# Power.net
KiCad netlist of a schematic drawn in Altium Designer
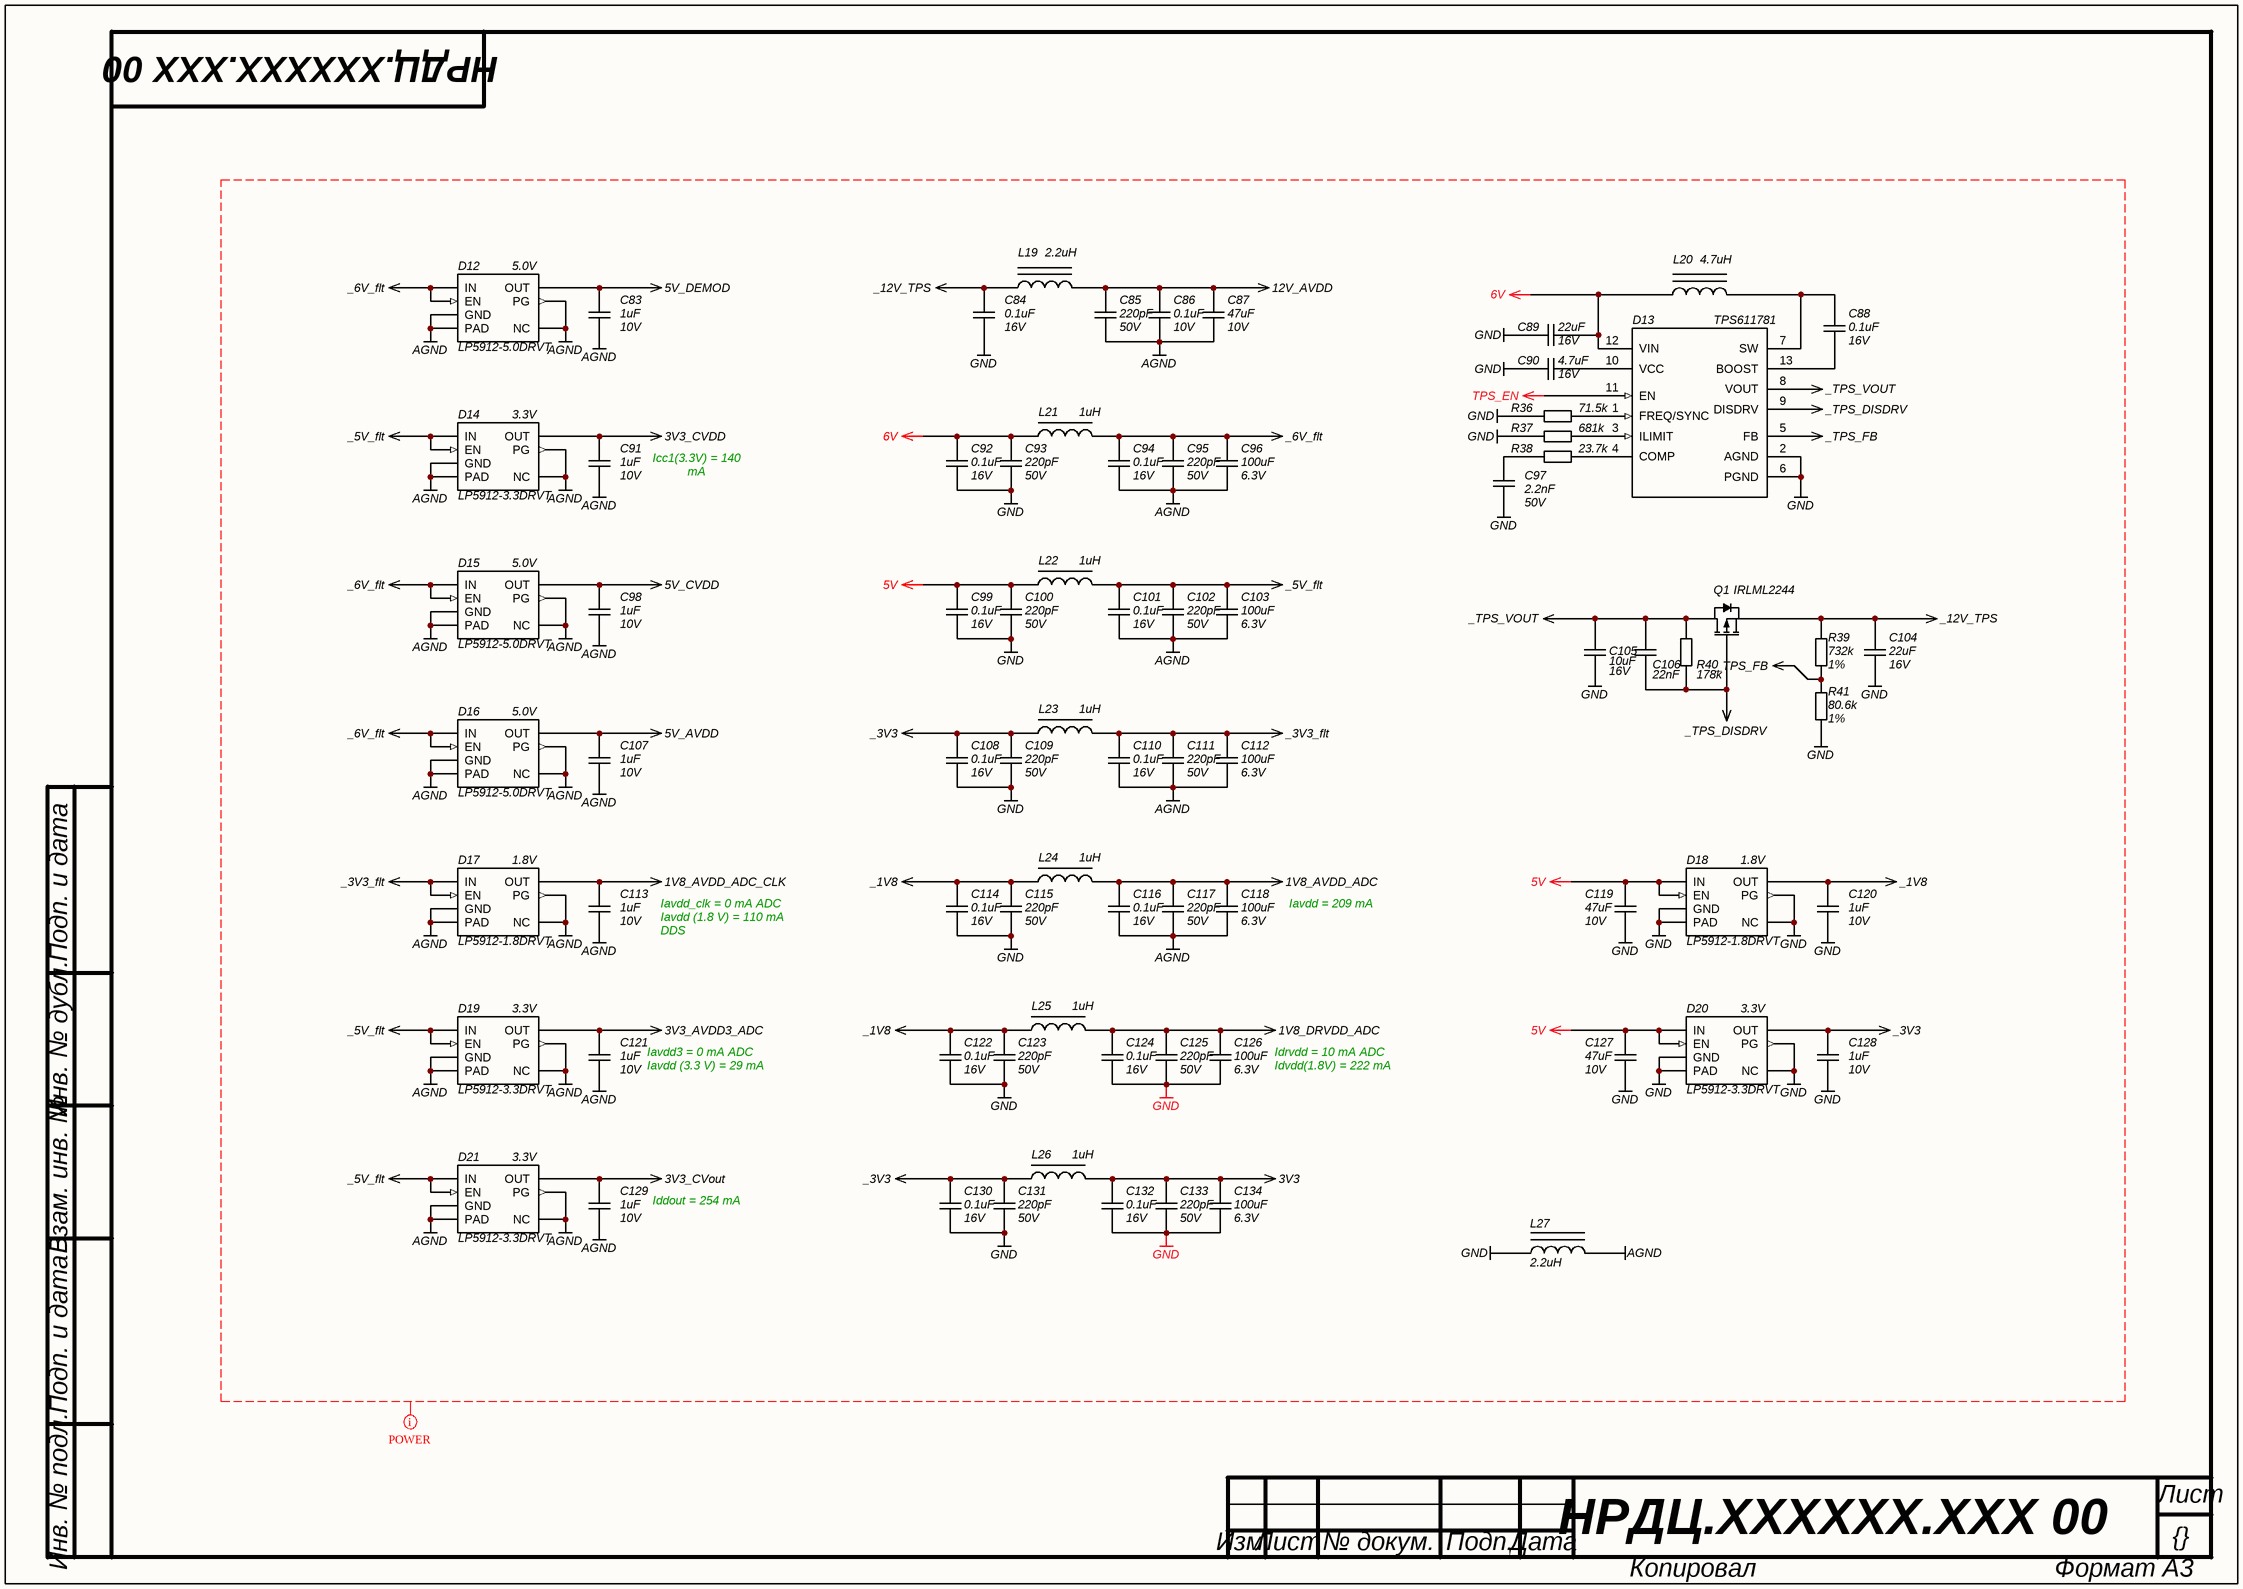
[diagram p0: Power.SchDoc]

(export (version "E")
  (design (tool "Eeschema 10.0.6"))
  (components
    (comp (ref "C83")
      (value "1uF")
      (footprint "C0805")
      (description "SMD Capacitor")
      (fields
        (field (name "MANUFACTURER") "Murata")
        (field (name "TOLERANCE") "10%")
        (field (name "VOLTAGE") "10V")
      )
      (libsource (lib "Kintex_SDR") (part "CAP"))
    )
    (comp (ref "C84")
      (value "0.1uF")
      (footprint "C0402")
      (description "SMD Capacitor")
      (fields
        (field (name "MANUFACTURER") "Murata")
        (field (name "TOLERANCE") "±10%")
        (field (name "VOLTAGE") "16V")
      )
      (libsource (lib "Kintex_SDR") (part "CAP"))
    )
    (comp (ref "C85")
      (value "220pF")
      (footprint "C0603")
      (description "SMD Capacitor")
      (fields
        (field (name "MANUFACTURER") "Murata")
        (field (name "TOLERANCE") "10%")
        (field (name "VOLTAGE") "50V")
      )
      (libsource (lib "Kintex_SDR") (part "CAP"))
    )
    (comp (ref "C86")
      (value "0.1uF")
      (footprint "C0402")
      (description "SMD Capacitor")
      (fields
        (field (name "MANUFACTURER") "Murata")
        (field (name "TOLERANCE") "10%")
        (field (name "VOLTAGE") "10V")
      )
      (libsource (lib "Kintex_SDR") (part "CAP"))
    )
    (comp (ref "C87")
      (value "47uF")
      (footprint "C1210")
      (description "SMD Capacitor")
      (fields
        (field (name "MANUFACTURER") "Murata")
        (field (name "TOLERANCE") "10%")
        (field (name "VOLTAGE") "10V")
      )
      (libsource (lib "Kintex_SDR") (part "CAP uF"))
    )
    (comp (ref "C88")
      (value "0.1uF")
      (footprint "C0402")
      (description "SMD Capacitor")
      (fields
        (field (name "MANUFACTURER") "Murata")
        (field (name "TOLERANCE") "±10%")
        (field (name "VOLTAGE") "16V")
      )
      (libsource (lib "Kintex_SDR") (part "CAP"))
    )
    (comp (ref "C89")
      (value "22uF")
      (footprint "C0805")
      (description "SMD Capacitor")
      (fields
        (field (name "MANUFACTURER") "Murata")
        (field (name "TOLERANCE") "±20%")
        (field (name "VOLTAGE") "16V")
      )
      (libsource (lib "Kintex_SDR") (part "CAP uF"))
    )
    (comp (ref "C90")
      (value "4.7uF")
      (footprint "C0603")
      (description "SMD Capacitor")
      (fields
        (field (name "MANUFACTURER") "Murata")
        (field (name "TOLERANCE") "10%")
        (field (name "VOLTAGE") "16V")
      )
      (libsource (lib "Kintex_SDR") (part "CAP"))
    )
    (comp (ref "C91")
      (value "1uF")
      (footprint "C0805")
      (description "SMD Capacitor")
      (fields
        (field (name "MANUFACTURER") "Murata")
        (field (name "TOLERANCE") "10%")
        (field (name "VOLTAGE") "10V")
      )
      (libsource (lib "Kintex_SDR") (part "CAP"))
    )
    (comp (ref "C92")
      (value "0.1uF")
      (footprint "C0603")
      (description "SMD Capacitor")
      (fields
        (field (name "MANUFACTURER") "Murata")
        (field (name "TOLERANCE") "10%")
        (field (name "VOLTAGE") "16V")
      )
      (libsource (lib "Kintex_SDR") (part "CAP"))
    )
    (comp (ref "C93")
      (value "220pF")
      (footprint "C0603")
      (description "SMD Capacitor")
      (fields
        (field (name "MANUFACTURER") "Murata")
        (field (name "TOLERANCE") "10%")
        (field (name "VOLTAGE") "50V")
      )
      (libsource (lib "Kintex_SDR") (part "CAP"))
    )
    (comp (ref "C94")
      (value "0.1uF")
      (footprint "C0603")
      (description "SMD Capacitor")
      (fields
        (field (name "MANUFACTURER") "Murata")
        (field (name "TOLERANCE") "10%")
        (field (name "VOLTAGE") "16V")
      )
      (libsource (lib "Kintex_SDR") (part "CAP"))
    )
    (comp (ref "C95")
      (value "220pF")
      (footprint "C0603")
      (description "SMD Capacitor")
      (fields
        (field (name "MANUFACTURER") "Murata")
        (field (name "TOLERANCE") "10%")
        (field (name "VOLTAGE") "50V")
      )
      (libsource (lib "Kintex_SDR") (part "CAP"))
    )
    (comp (ref "C96")
      (value "100uF")
      (footprint "C1210")
      (description "SMD Capacitor")
      (fields
        (field (name "MANUFACTURER") "Murata")
        (field (name "TOLERANCE") "20%")
        (field (name "VOLTAGE") "6.3V")
      )
      (libsource (lib "Kintex_SDR") (part "CAP uF"))
    )
    (comp (ref "C97")
      (value "2.2nF")
      (footprint "C0603")
      (description "SMD Capacitor")
      (fields
        (field (name "MANUFACTURER") "Murata")
        (field (name "TOLERANCE") "±5%")
        (field (name "VOLTAGE") "50V")
      )
      (libsource (lib "Kintex_SDR") (part "CAP"))
    )
    (comp (ref "C98")
      (value "1uF")
      (footprint "C0805")
      (description "SMD Capacitor")
      (fields
        (field (name "MANUFACTURER") "Murata")
        (field (name "TOLERANCE") "10%")
        (field (name "VOLTAGE") "10V")
      )
      (libsource (lib "Kintex_SDR") (part "CAP"))
    )
    (comp (ref "C99")
      (value "0.1uF")
      (footprint "C0603")
      (description "SMD Capacitor")
      (fields
        (field (name "MANUFACTURER") "Murata")
        (field (name "TOLERANCE") "10%")
        (field (name "VOLTAGE") "16V")
      )
      (libsource (lib "Kintex_SDR") (part "CAP"))
    )
    (comp (ref "C100")
      (value "220pF")
      (footprint "C0603")
      (description "SMD Capacitor")
      (fields
        (field (name "MANUFACTURER") "Murata")
        (field (name "TOLERANCE") "10%")
        (field (name "VOLTAGE") "50V")
      )
      (libsource (lib "Kintex_SDR") (part "CAP"))
    )
    (comp (ref "C101")
      (value "0.1uF")
      (footprint "C0603")
      (description "SMD Capacitor")
      (fields
        (field (name "MANUFACTURER") "Murata")
        (field (name "TOLERANCE") "10%")
        (field (name "VOLTAGE") "16V")
      )
      (libsource (lib "Kintex_SDR") (part "CAP"))
    )
    (comp (ref "C102")
      (value "220pF")
      (footprint "C0603")
      (description "SMD Capacitor")
      (fields
        (field (name "MANUFACTURER") "Murata")
        (field (name "TOLERANCE") "10%")
        (field (name "VOLTAGE") "50V")
      )
      (libsource (lib "Kintex_SDR") (part "CAP"))
    )
    (comp (ref "C103")
      (value "100uF")
      (footprint "C1210")
      (description "SMD Capacitor")
      (fields
        (field (name "MANUFACTURER") "Murata")
        (field (name "TOLERANCE") "20%")
        (field (name "VOLTAGE") "6.3V")
      )
      (libsource (lib "Kintex_SDR") (part "CAP uF"))
    )
    (comp (ref "C104")
      (value "22uF")
      (footprint "C0805")
      (description "SMD Capacitor")
      (fields
        (field (name "MANUFACTURER") "Murata")
        (field (name "TOLERANCE") "±20%")
        (field (name "VOLTAGE") "16V")
      )
      (libsource (lib "Kintex_SDR") (part "CAP uF"))
    )
    (comp (ref "C105")
      (value "10uF")
      (footprint "C0805")
      (description "SMD Capacitor")
      (fields
        (field (name "MANUFACTURER") "Murata")
        (field (name "TOLERANCE") "±10%")
        (field (name "VOLTAGE") "16V")
      )
      (libsource (lib "Kintex_SDR") (part "CAP uF"))
    )
    (comp (ref "C106")
      (value "22nF")
      (footprint "C0402")
      (description "SMD Capacitor")
      (fields (field (name "MANUFACTURER") "Murata") (field (name "TOLERANCE") "10%"))
      (libsource (lib "Kintex_SDR") (part "CAP"))
    )
    (comp (ref "C107")
      (value "1uF")
      (footprint "C0805")
      (description "SMD Capacitor")
      (fields
        (field (name "MANUFACTURER") "Murata")
        (field (name "TOLERANCE") "10%")
        (field (name "VOLTAGE") "10V")
      )
      (libsource (lib "Kintex_SDR") (part "CAP"))
    )
    (comp (ref "C108")
      (value "0.1uF")
      (footprint "C0603")
      (description "SMD Capacitor")
      (fields
        (field (name "MANUFACTURER") "Murata")
        (field (name "TOLERANCE") "10%")
        (field (name "VOLTAGE") "16V")
      )
      (libsource (lib "Kintex_SDR") (part "CAP"))
    )
    (comp (ref "C109")
      (value "220pF")
      (footprint "C0603")
      (description "SMD Capacitor")
      (fields
        (field (name "MANUFACTURER") "Murata")
        (field (name "TOLERANCE") "10%")
        (field (name "VOLTAGE") "50V")
      )
      (libsource (lib "Kintex_SDR") (part "CAP"))
    )
    (comp (ref "C110")
      (value "0.1uF")
      (footprint "C0603")
      (description "SMD Capacitor")
      (fields
        (field (name "MANUFACTURER") "Murata")
        (field (name "TOLERANCE") "10%")
        (field (name "VOLTAGE") "16V")
      )
      (libsource (lib "Kintex_SDR") (part "CAP"))
    )
    (comp (ref "C111")
      (value "220pF")
      (footprint "C0603")
      (description "SMD Capacitor")
      (fields
        (field (name "MANUFACTURER") "Murata")
        (field (name "TOLERANCE") "10%")
        (field (name "VOLTAGE") "50V")
      )
      (libsource (lib "Kintex_SDR") (part "CAP"))
    )
    (comp (ref "C112")
      (value "100uF")
      (footprint "C1210")
      (description "SMD Capacitor")
      (fields
        (field (name "MANUFACTURER") "Murata")
        (field (name "TOLERANCE") "20%")
        (field (name "VOLTAGE") "6.3V")
      )
      (libsource (lib "Kintex_SDR") (part "CAP uF"))
    )
    (comp (ref "C113")
      (value "1uF")
      (footprint "C0805")
      (description "SMD Capacitor")
      (fields
        (field (name "MANUFACTURER") "Murata")
        (field (name "TOLERANCE") "10%")
        (field (name "VOLTAGE") "10V")
      )
      (libsource (lib "Kintex_SDR") (part "CAP"))
    )
    (comp (ref "C114")
      (value "0.1uF")
      (footprint "C0603")
      (description "SMD Capacitor")
      (fields
        (field (name "MANUFACTURER") "Murata")
        (field (name "TOLERANCE") "10%")
        (field (name "VOLTAGE") "16V")
      )
      (libsource (lib "Kintex_SDR") (part "CAP"))
    )
    (comp (ref "C115")
      (value "220pF")
      (footprint "C0603")
      (description "SMD Capacitor")
      (fields
        (field (name "MANUFACTURER") "Murata")
        (field (name "TOLERANCE") "10%")
        (field (name "VOLTAGE") "50V")
      )
      (libsource (lib "Kintex_SDR") (part "CAP"))
    )
    (comp (ref "C116")
      (value "0.1uF")
      (footprint "C0603")
      (description "SMD Capacitor")
      (fields
        (field (name "MANUFACTURER") "Murata")
        (field (name "TOLERANCE") "10%")
        (field (name "VOLTAGE") "16V")
      )
      (libsource (lib "Kintex_SDR") (part "CAP"))
    )
    (comp (ref "C117")
      (value "220pF")
      (footprint "C0603")
      (description "SMD Capacitor")
      (fields
        (field (name "MANUFACTURER") "Murata")
        (field (name "TOLERANCE") "10%")
        (field (name "VOLTAGE") "50V")
      )
      (libsource (lib "Kintex_SDR") (part "CAP"))
    )
    (comp (ref "C118")
      (value "100uF")
      (footprint "C1210")
      (description "SMD Capacitor")
      (fields
        (field (name "MANUFACTURER") "Murata")
        (field (name "TOLERANCE") "20%")
        (field (name "VOLTAGE") "6.3V")
      )
      (libsource (lib "Kintex_SDR") (part "CAP uF"))
    )
    (comp (ref "C119")
      (value "47uF")
      (footprint "C1210")
      (description "SMD Capacitor")
      (fields
        (field (name "MANUFACTURER") "Murata")
        (field (name "TOLERANCE") "10%")
        (field (name "VOLTAGE") "10V")
      )
      (libsource (lib "Kintex_SDR") (part "CAP uF"))
    )
    (comp (ref "C120")
      (value "1uF")
      (footprint "C0805")
      (description "SMD Capacitor")
      (fields
        (field (name "MANUFACTURER") "Murata")
        (field (name "TOLERANCE") "10%")
        (field (name "VOLTAGE") "10V")
      )
      (libsource (lib "Kintex_SDR") (part "CAP"))
    )
    (comp (ref "C121")
      (value "1uF")
      (footprint "C0805")
      (description "SMD Capacitor")
      (fields
        (field (name "MANUFACTURER") "Murata")
        (field (name "TOLERANCE") "10%")
        (field (name "VOLTAGE") "10V")
      )
      (libsource (lib "Kintex_SDR") (part "CAP"))
    )
    (comp (ref "C122")
      (value "0.1uF")
      (footprint "C0603")
      (description "SMD Capacitor")
      (fields
        (field (name "MANUFACTURER") "Murata")
        (field (name "TOLERANCE") "10%")
        (field (name "VOLTAGE") "16V")
      )
      (libsource (lib "Kintex_SDR") (part "CAP"))
    )
    (comp (ref "C123")
      (value "220pF")
      (footprint "C0603")
      (description "SMD Capacitor")
      (fields
        (field (name "MANUFACTURER") "Murata")
        (field (name "TOLERANCE") "10%")
        (field (name "VOLTAGE") "50V")
      )
      (libsource (lib "Kintex_SDR") (part "CAP"))
    )
    (comp (ref "C124")
      (value "0.1uF")
      (footprint "C0603")
      (description "SMD Capacitor")
      (fields
        (field (name "MANUFACTURER") "Murata")
        (field (name "TOLERANCE") "10%")
        (field (name "VOLTAGE") "16V")
      )
      (libsource (lib "Kintex_SDR") (part "CAP"))
    )
    (comp (ref "C125")
      (value "220pF")
      (footprint "C0603")
      (description "SMD Capacitor")
      (fields
        (field (name "MANUFACTURER") "Murata")
        (field (name "TOLERANCE") "10%")
        (field (name "VOLTAGE") "50V")
      )
      (libsource (lib "Kintex_SDR") (part "CAP"))
    )
    (comp (ref "C126")
      (value "100uF")
      (footprint "C1210")
      (description "SMD Capacitor")
      (fields
        (field (name "MANUFACTURER") "Murata")
        (field (name "TOLERANCE") "20%")
        (field (name "VOLTAGE") "6.3V")
      )
      (libsource (lib "Kintex_SDR") (part "CAP uF"))
    )
    (comp (ref "C127")
      (value "47uF")
      (footprint "C1210")
      (description "SMD Capacitor")
      (fields
        (field (name "MANUFACTURER") "Murata")
        (field (name "TOLERANCE") "10%")
        (field (name "VOLTAGE") "10V")
      )
      (libsource (lib "Kintex_SDR") (part "CAP uF"))
    )
    (comp (ref "C128")
      (value "1uF")
      (footprint "C0805")
      (description "SMD Capacitor")
      (fields
        (field (name "MANUFACTURER") "Murata")
        (field (name "TOLERANCE") "10%")
        (field (name "VOLTAGE") "10V")
      )
      (libsource (lib "Kintex_SDR") (part "CAP"))
    )
    (comp (ref "C129")
      (value "1uF")
      (footprint "C0805")
      (description "SMD Capacitor")
      (fields
        (field (name "MANUFACTURER") "Murata")
        (field (name "TOLERANCE") "10%")
        (field (name "VOLTAGE") "10V")
      )
      (libsource (lib "Kintex_SDR") (part "CAP"))
    )
    (comp (ref "C130")
      (value "0.1uF")
      (footprint "C0603")
      (description "SMD Capacitor")
      (fields
        (field (name "MANUFACTURER") "Murata")
        (field (name "TOLERANCE") "10%")
        (field (name "VOLTAGE") "16V")
      )
      (libsource (lib "Kintex_SDR") (part "CAP"))
    )
    (comp (ref "C131")
      (value "220pF")
      (footprint "C0603")
      (description "SMD Capacitor")
      (fields
        (field (name "MANUFACTURER") "Murata")
        (field (name "TOLERANCE") "10%")
        (field (name "VOLTAGE") "50V")
      )
      (libsource (lib "Kintex_SDR") (part "CAP"))
    )
    (comp (ref "C132")
      (value "0.1uF")
      (footprint "C0603")
      (description "SMD Capacitor")
      (fields
        (field (name "MANUFACTURER") "Murata")
        (field (name "TOLERANCE") "10%")
        (field (name "VOLTAGE") "16V")
      )
      (libsource (lib "Kintex_SDR") (part "CAP"))
    )
    (comp (ref "C133")
      (value "220pF")
      (footprint "C0603")
      (description "SMD Capacitor")
      (fields
        (field (name "MANUFACTURER") "Murata")
        (field (name "TOLERANCE") "10%")
        (field (name "VOLTAGE") "50V")
      )
      (libsource (lib "Kintex_SDR") (part "CAP"))
    )
    (comp (ref "C134")
      (value "100uF")
      (footprint "C1210")
      (description "SMD Capacitor")
      (fields
        (field (name "MANUFACTURER") "Murata")
        (field (name "TOLERANCE") "20%")
        (field (name "VOLTAGE") "6.3V")
      )
      (libsource (lib "Kintex_SDR") (part "CAP uF"))
    )
    (comp (ref "D12")
      (value "LP5912")
      (footprint "DBLib:WSON-6")
      (description "LP5912 500-mA Low-Noise, Low-IQ LDO")
      (fields
        (field (name "MANUFACTURER") "Texas Instruments")
        (field (name "NAME") "LP5912-5.0DRVT")
        (field (name "VOLTAGE") "5.0V")
      )
      (libsource (lib "DBLib") (part "LP5912"))
    )
    (comp (ref "D13")
      (value "TPS611781")
      (footprint "DBLib:TPS611781x")
      (description "10-A Fully-Integrated Synchronous Boost with Load Disconnect Control")
      (fields (field (name "MANUFACTURER") "Texas Instruments") (field (name "VOLTAGE") "4.5 V to 20 V"))
      (libsource (lib "DBLib") (part "TPS611781"))
    )
    (comp (ref "D14")
      (value "LP5912")
      (footprint "DBLib:WSON-6")
      (description "LP5912 500-mA Low-Noise, Low-IQ LDO")
      (fields
        (field (name "MANUFACTURER") "Texas Instruments")
        (field (name "NAME") "LP5912-3.3DRVT")
        (field (name "VOLTAGE") "3.3V")
      )
      (libsource (lib "DBLib") (part "LP5912"))
    )
    (comp (ref "D15")
      (value "LP5912")
      (footprint "DBLib:WSON-6")
      (description "LP5912 500-mA Low-Noise, Low-IQ LDO")
      (fields
        (field (name "MANUFACTURER") "Texas Instruments")
        (field (name "NAME") "LP5912-5.0DRVT")
        (field (name "VOLTAGE") "5.0V")
      )
      (libsource (lib "DBLib") (part "LP5912"))
    )
    (comp (ref "D16")
      (value "LP5912")
      (footprint "DBLib:WSON-6")
      (description "LP5912 500-mA Low-Noise, Low-IQ LDO")
      (fields
        (field (name "MANUFACTURER") "Texas Instruments")
        (field (name "NAME") "LP5912-5.0DRVT")
        (field (name "VOLTAGE") "5.0V")
      )
      (libsource (lib "DBLib") (part "LP5912"))
    )
    (comp (ref "D17")
      (value "LP5912")
      (footprint "DBLib:WSON-6")
      (description "LP5912 500-mA Low-Noise, Low-IQ LDO")
      (fields
        (field (name "MANUFACTURER") "Texas Instruments")
        (field (name "NAME") "LP5912-1.8DRVT")
        (field (name "VOLTAGE") "1.8V")
      )
      (libsource (lib "DBLib") (part "LP5912"))
    )
    (comp (ref "D18")
      (value "LP5912")
      (footprint "DBLib:WSON-6")
      (description "LP5912 500-mA Low-Noise, Low-IQ LDO")
      (fields
        (field (name "MANUFACTURER") "Texas Instruments")
        (field (name "NAME") "LP5912-1.8DRVT")
        (field (name "VOLTAGE") "1.8V")
      )
      (libsource (lib "DBLib") (part "LP5912"))
    )
    (comp (ref "D19")
      (value "LP5912")
      (footprint "DBLib:WSON-6")
      (description "LP5912 500-mA Low-Noise, Low-IQ LDO")
      (fields
        (field (name "MANUFACTURER") "Texas Instruments")
        (field (name "NAME") "LP5912-3.3DRVT")
        (field (name "VOLTAGE") "3.3V")
      )
      (libsource (lib "DBLib") (part "LP5912"))
    )
    (comp (ref "D20")
      (value "LP5912")
      (footprint "DBLib:WSON-6")
      (description "LP5912 500-mA Low-Noise, Low-IQ LDO")
      (fields
        (field (name "MANUFACTURER") "Texas Instruments")
        (field (name "NAME") "LP5912-3.3DRVT")
        (field (name "VOLTAGE") "3.3V")
      )
      (libsource (lib "DBLib") (part "LP5912"))
    )
    (comp (ref "D21")
      (value "LP5912")
      (footprint "DBLib:WSON-6")
      (description "LP5912 500-mA Low-Noise, Low-IQ LDO")
      (fields
        (field (name "MANUFACTURER") "Texas Instruments")
        (field (name "NAME") "LP5912-3.3DRVT")
        (field (name "VOLTAGE") "3.3V")
      )
      (libsource (lib "DBLib") (part "LP5912"))
    )
    (comp (ref "L19")
      (value "2.2uH")
      (footprint "XAL4020")
      (description "Magnetic-Core Inductor")
      (fields (field (name "MANUFACTURER") "Coilcraft") (field (name "TOLERANCE") "±30%"))
      (libsource (lib "Kintex_SDR") (part "Inductor PWR"))
    )
    (comp (ref "L20")
      (value "4.7uH")
      (footprint "XAL4030")
      (description "Magnetic-Core Inductor")
      (fields (field (name "MANUFACTURER") "Coilcraft") (field (name "TOLERANCE") "±30%"))
      (libsource (lib "Kintex_SDR") (part "Inductor PWR"))
    )
    (comp (ref "L21")
      (value "1uH")
      (footprint "L1210_Murata LQH")
      (description "Inductor Power Lines")
      (fields (field (name "MANUFACTURER") "Murata") (field (name "TOLERANCE") "5%"))
      (libsource (lib "Kintex_SDR") (part "Inductor LF"))
    )
    (comp (ref "L22")
      (value "1uH")
      (footprint "L1210_Murata LQH")
      (description "Inductor Power Lines")
      (fields (field (name "MANUFACTURER") "Murata") (field (name "TOLERANCE") "5%"))
      (libsource (lib "Kintex_SDR") (part "Inductor LF"))
    )
    (comp (ref "L23")
      (value "1uH")
      (footprint "L1210_Murata LQH")
      (description "Inductor Power Lines")
      (fields (field (name "MANUFACTURER") "Murata") (field (name "TOLERANCE") "5%"))
      (libsource (lib "Kintex_SDR") (part "Inductor LF"))
    )
    (comp (ref "L24")
      (value "1uH")
      (footprint "L1210_Murata LQH")
      (description "Inductor Power Lines")
      (fields (field (name "MANUFACTURER") "Murata") (field (name "TOLERANCE") "5%"))
      (libsource (lib "Kintex_SDR") (part "Inductor LF"))
    )
    (comp (ref "L25")
      (value "1uH")
      (footprint "L1210_Murata LQH")
      (description "Inductor Power Lines")
      (fields (field (name "MANUFACTURER") "Murata") (field (name "TOLERANCE") "5%"))
      (libsource (lib "Kintex_SDR") (part "Inductor LF"))
    )
    (comp (ref "L26")
      (value "1uH")
      (footprint "L1210_Murata LQH")
      (description "Inductor Power Lines")
      (fields (field (name "MANUFACTURER") "Murata") (field (name "TOLERANCE") "5%"))
      (libsource (lib "Kintex_SDR") (part "Inductor LF"))
    )
    (comp (ref "L27")
      (value "2.2uH")
      (footprint "XAL4020")
      (description "Magnetic-Core Inductor")
      (fields (field (name "MANUFACTURER") "Coilcraft") (field (name "TOLERANCE") "±30%"))
      (libsource (lib "Kintex_SDR") (part "Inductor PWR"))
    )
    (comp (ref "Q1")
      (value "IRLML2244")
      (footprint "DBLib:SOT-23")
      (description "P-Channel MOSFET")
      (fields (field (name "VOLTAGE") "-20V"))
      (libsource (lib "DBLib") (part "IRLML2244"))
    )
    (comp (ref "R36")
      (value "71.5k")
      (footprint "R0402")
      (description "SMD Resistor")
      (fields (field (name "POWER") "0.063 Wt") (field (name "TOLERANCE") "1%"))
      (libsource (lib "Kintex_SDR") (part "RES"))
    )
    (comp (ref "R37")
      (value "681k")
      (footprint "R0402")
      (description "SMD Resistor")
      (fields (field (name "POWER") "0.063 Wt") (field (name "TOLERANCE") "1%"))
      (libsource (lib "Kintex_SDR") (part "RES"))
    )
    (comp (ref "R38")
      (value "23.7k")
      (footprint "R0603")
      (description "SMD Resistor")
      (fields (field (name "POWER") "0.1 Wt") (field (name "TOLERANCE") "1%"))
      (libsource (lib "Kintex_SDR") (part "RES"))
    )
    (comp (ref "R39")
      (value "732k")
      (footprint "R0402")
      (description "SMD Resistor")
      (fields
        (field (name "POWER") "0.063 Wt")
        (field (name "TOLERANCE") "1%")
        (field (name "MANUFACTURER") "Panasonic Electronic Components")
      )
      (libsource (lib "") (part "RES_1"))
    )
    (comp (ref "R40")
      (value "178k")
      (footprint "R0402")
      (description "SMD Resistor")
      (fields (field (name "POWER") "0.063 Wt") (field (name "TOLERANCE") "1%"))
      (libsource (lib "") (part "RES_1"))
    )
    (comp (ref "R41")
      (value "80.6k")
      (footprint "R0402")
      (description "SMD Resistor")
      (fields
        (field (name "POWER") "0.063 Wt")
        (field (name "TOLERANCE") "1%")
        (field (name "MANUFACTURER") "Panasonic Electronic Components")
      )
      (libsource (lib "") (part "RES_1"))
    )
  )
  (nets
    (net (code "1") (name "1V8_AVDD_ADC") (class "Default")
      (node (ref "C116") (pin "2") (pinfunction "2_2") (pintype "passive"))
      (node (ref "C117") (pin "2") (pinfunction "2_2") (pintype "passive"))
      (node (ref "C118") (pin "2") (pinfunction "2_2") (pintype "passive"))
      (node (ref "L24") (pin "2") (pinfunction "2_2") (pintype "passive"))
    )
    (net (code "2") (name "1V8_AVDD_ADC_CLK") (class "Default")
      (node (ref "C113") (pin "1") (pinfunction "1_1") (pintype "passive"))
      (node (ref "D17") (pin "1") (pinfunction "OUT_1") (pintype "passive"))
    )
    (net (code "3") (name "1V8_DRVDD_ADC") (class "Default")
      (node (ref "C124") (pin "2") (pinfunction "2_2") (pintype "passive"))
      (node (ref "C125") (pin "2") (pinfunction "2_2") (pintype "passive"))
      (node (ref "C126") (pin "2") (pinfunction "2_2") (pintype "passive"))
      (node (ref "L25") (pin "2") (pinfunction "2_2") (pintype "passive"))
    )
    (net (code "4") (name "3V3") (class "Default")
      (node (ref "C132") (pin "2") (pinfunction "2_2") (pintype "passive"))
      (node (ref "C133") (pin "2") (pinfunction "2_2") (pintype "passive"))
      (node (ref "C134") (pin "2") (pinfunction "2_2") (pintype "passive"))
      (node (ref "L26") (pin "2") (pinfunction "2_2") (pintype "passive"))
    )
    (net (code "5") (name "3V3_AVDD3_ADC") (class "Default")
      (node (ref "C121") (pin "1") (pinfunction "1_1") (pintype "passive"))
      (node (ref "D19") (pin "1") (pinfunction "OUT_1") (pintype "passive"))
    )
    (net (code "6") (name "3V3_CVDD") (class "Default")
      (node (ref "C91") (pin "1") (pinfunction "1_1") (pintype "passive"))
      (node (ref "D14") (pin "1") (pinfunction "OUT_1") (pintype "passive"))
    )
    (net (code "7") (name "3V3_CVout") (class "Default")
      (node (ref "C129") (pin "1") (pinfunction "1_1") (pintype "passive"))
      (node (ref "D21") (pin "1") (pinfunction "OUT_1") (pintype "passive"))
    )
    (net (code "8") (name "5V") (class "Default")
      (node (ref "C100") (pin "2") (pinfunction "2_2") (pintype "passive"))
      (node (ref "C119") (pin "2") (pinfunction "2_2") (pintype "passive"))
      (node (ref "C127") (pin "2") (pinfunction "2_2") (pintype "passive"))
      (node (ref "C99") (pin "2") (pinfunction "2_2") (pintype "passive"))
      (node (ref "D18") (pin "4") (pinfunction "EN_4") (pintype "input"))
      (node (ref "D18") (pin "6") (pinfunction "IN_6") (pintype "passive"))
      (node (ref "D20") (pin "4") (pinfunction "EN_4") (pintype "input"))
      (node (ref "D20") (pin "6") (pinfunction "IN_6") (pintype "passive"))
      (node (ref "L22") (pin "1") (pinfunction "1_1") (pintype "passive"))
    )
    (net (code "9") (name "5V_AVDD") (class "Default")
      (node (ref "C107") (pin "1") (pinfunction "1_1") (pintype "passive"))
      (node (ref "D16") (pin "1") (pinfunction "OUT_1") (pintype "passive"))
    )
    (net (code "10") (name "5V_CVDD") (class "Default")
      (node (ref "C98") (pin "1") (pinfunction "1_1") (pintype "passive"))
      (node (ref "D15") (pin "1") (pinfunction "OUT_1") (pintype "passive"))
    )
    (net (code "11") (name "5V_DEMOD") (class "Default")
      (node (ref "C83") (pin "1") (pinfunction "1_1") (pintype "passive"))
      (node (ref "D12") (pin "1") (pinfunction "OUT_1") (pintype "passive"))
    )
    (net (code "12") (name "6V") (class "Default")
      (node (ref "C89") (pin "1") (pinfunction "1_1") (pintype "passive"))
      (node (ref "C92") (pin "2") (pinfunction "2_2") (pintype "passive"))
      (node (ref "C93") (pin "2") (pinfunction "2_2") (pintype "passive"))
      (node (ref "D13") (pin "12") (pinfunction "VIN_12") (pintype "passive"))
      (node (ref "L20") (pin "1") (pinfunction "1_1") (pintype "passive"))
      (node (ref "L21") (pin "1") (pinfunction "1_1") (pintype "passive"))
    )
    (net (code "13") (name "12V_AVDD") (class "Default")
      (node (ref "C85") (pin "2") (pinfunction "2_2") (pintype "passive"))
      (node (ref "C86") (pin "2") (pinfunction "2_2") (pintype "passive"))
      (node (ref "C87") (pin "2") (pinfunction "2_2") (pintype "passive"))
      (node (ref "L19") (pin "2") (pinfunction "2_2") (pintype "passive"))
    )
    (net (code "14") (name "AGND") (class "Default")
      (node (ref "C101") (pin "1") (pinfunction "1_1") (pintype "passive"))
      (node (ref "C102") (pin "1") (pinfunction "1_1") (pintype "passive"))
      (node (ref "C103") (pin "1") (pinfunction "1_1") (pintype "passive"))
      (node (ref "C107") (pin "2") (pinfunction "2_2") (pintype "passive"))
      (node (ref "C110") (pin "1") (pinfunction "1_1") (pintype "passive"))
      (node (ref "C111") (pin "1") (pinfunction "1_1") (pintype "passive"))
      (node (ref "C112") (pin "1") (pinfunction "1_1") (pintype "passive"))
      (node (ref "C113") (pin "2") (pinfunction "2_2") (pintype "passive"))
      (node (ref "C116") (pin "1") (pinfunction "1_1") (pintype "passive"))
      (node (ref "C117") (pin "1") (pinfunction "1_1") (pintype "passive"))
      (node (ref "C118") (pin "1") (pinfunction "1_1") (pintype "passive"))
      (node (ref "C121") (pin "2") (pinfunction "2_2") (pintype "passive"))
      (node (ref "C129") (pin "2") (pinfunction "2_2") (pintype "passive"))
      (node (ref "C83") (pin "2") (pinfunction "2_2") (pintype "passive"))
      (node (ref "C85") (pin "1") (pinfunction "1_1") (pintype "passive"))
      (node (ref "C86") (pin "1") (pinfunction "1_1") (pintype "passive"))
      (node (ref "C87") (pin "1") (pinfunction "1_1") (pintype "passive"))
      (node (ref "C91") (pin "2") (pinfunction "2_2") (pintype "passive"))
      (node (ref "C94") (pin "1") (pinfunction "1_1") (pintype "passive"))
      (node (ref "C95") (pin "1") (pinfunction "1_1") (pintype "passive"))
      (node (ref "C96") (pin "1") (pinfunction "1_1") (pintype "passive"))
      (node (ref "C98") (pin "2") (pinfunction "2_2") (pintype "passive"))
      (node (ref "D12") (pin "0") (pinfunction "PAD_0") (pintype "passive"))
      (node (ref "D12") (pin "2") (pinfunction "NC_2") (pintype "passive"))
      (node (ref "D12") (pin "3") (pinfunction "PG_3") (pintype "output"))
      (node (ref "D12") (pin "5") (pinfunction "GND_5") (pintype "passive"))
      (node (ref "D14") (pin "0") (pinfunction "PAD_0") (pintype "passive"))
      (node (ref "D14") (pin "2") (pinfunction "NC_2") (pintype "passive"))
      (node (ref "D14") (pin "3") (pinfunction "PG_3") (pintype "output"))
      (node (ref "D14") (pin "5") (pinfunction "GND_5") (pintype "passive"))
      (node (ref "D15") (pin "0") (pinfunction "PAD_0") (pintype "passive"))
      (node (ref "D15") (pin "2") (pinfunction "NC_2") (pintype "passive"))
      (node (ref "D15") (pin "3") (pinfunction "PG_3") (pintype "output"))
      (node (ref "D15") (pin "5") (pinfunction "GND_5") (pintype "passive"))
      (node (ref "D16") (pin "0") (pinfunction "PAD_0") (pintype "passive"))
      (node (ref "D16") (pin "2") (pinfunction "NC_2") (pintype "passive"))
      (node (ref "D16") (pin "3") (pinfunction "PG_3") (pintype "output"))
      (node (ref "D16") (pin "5") (pinfunction "GND_5") (pintype "passive"))
      (node (ref "D17") (pin "0") (pinfunction "PAD_0") (pintype "passive"))
      (node (ref "D17") (pin "2") (pinfunction "NC_2") (pintype "passive"))
      (node (ref "D17") (pin "3") (pinfunction "PG_3") (pintype "output"))
      (node (ref "D17") (pin "5") (pinfunction "GND_5") (pintype "passive"))
      (node (ref "D19") (pin "0") (pinfunction "PAD_0") (pintype "passive"))
      (node (ref "D19") (pin "2") (pinfunction "NC_2") (pintype "passive"))
      (node (ref "D19") (pin "3") (pinfunction "PG_3") (pintype "output"))
      (node (ref "D19") (pin "5") (pinfunction "GND_5") (pintype "passive"))
      (node (ref "D21") (pin "0") (pinfunction "PAD_0") (pintype "passive"))
      (node (ref "D21") (pin "2") (pinfunction "NC_2") (pintype "passive"))
      (node (ref "D21") (pin "3") (pinfunction "PG_3") (pintype "output"))
      (node (ref "D21") (pin "5") (pinfunction "GND_5") (pintype "passive"))
      (node (ref "L27") (pin "2") (pinfunction "2_2") (pintype "passive"))
    )
    (net (code "15") (name "GND") (class "Default")
      (node (ref "C100") (pin "1") (pinfunction "1_1") (pintype "passive"))
      (node (ref "C104") (pin "1") (pinfunction "1_1") (pintype "passive"))
      (node (ref "C105") (pin "1") (pinfunction "1_1") (pintype "passive"))
      (node (ref "C108") (pin "1") (pinfunction "1_1") (pintype "passive"))
      (node (ref "C109") (pin "1") (pinfunction "1_1") (pintype "passive"))
      (node (ref "C114") (pin "1") (pinfunction "1_1") (pintype "passive"))
      (node (ref "C115") (pin "1") (pinfunction "1_1") (pintype "passive"))
      (node (ref "C119") (pin "1") (pinfunction "1_1") (pintype "passive"))
      (node (ref "C120") (pin "2") (pinfunction "2_2") (pintype "passive"))
      (node (ref "C122") (pin "1") (pinfunction "1_1") (pintype "passive"))
      (node (ref "C123") (pin "1") (pinfunction "1_1") (pintype "passive"))
      (node (ref "C124") (pin "1") (pinfunction "1_1") (pintype "passive"))
      (node (ref "C125") (pin "1") (pinfunction "1_1") (pintype "passive"))
      (node (ref "C126") (pin "1") (pinfunction "1_1") (pintype "passive"))
      (node (ref "C127") (pin "1") (pinfunction "1_1") (pintype "passive"))
      (node (ref "C128") (pin "2") (pinfunction "2_2") (pintype "passive"))
      (node (ref "C130") (pin "1") (pinfunction "1_1") (pintype "passive"))
      (node (ref "C131") (pin "1") (pinfunction "1_1") (pintype "passive"))
      (node (ref "C132") (pin "1") (pinfunction "1_1") (pintype "passive"))
      (node (ref "C133") (pin "1") (pinfunction "1_1") (pintype "passive"))
      (node (ref "C134") (pin "1") (pinfunction "1_1") (pintype "passive"))
      (node (ref "C84") (pin "1") (pinfunction "1_1") (pintype "passive"))
      (node (ref "C89") (pin "2") (pinfunction "2_2") (pintype "passive"))
      (node (ref "C90") (pin "2") (pinfunction "2_2") (pintype "passive"))
      (node (ref "C92") (pin "1") (pinfunction "1_1") (pintype "passive"))
      (node (ref "C93") (pin "1") (pinfunction "1_1") (pintype "passive"))
      (node (ref "C97") (pin "1") (pinfunction "1_1") (pintype "passive"))
      (node (ref "C99") (pin "1") (pinfunction "1_1") (pintype "passive"))
      (node (ref "D13") (pin "2") (pinfunction "AGND_2") (pintype "passive"))
      (node (ref "D13") (pin "6") (pinfunction "PGND_6") (pintype "passive"))
      (node (ref "D18") (pin "0") (pinfunction "PAD_0") (pintype "passive"))
      (node (ref "D18") (pin "2") (pinfunction "NC_2") (pintype "passive"))
      (node (ref "D18") (pin "3") (pinfunction "PG_3") (pintype "output"))
      (node (ref "D18") (pin "5") (pinfunction "GND_5") (pintype "passive"))
      (node (ref "D20") (pin "0") (pinfunction "PAD_0") (pintype "passive"))
      (node (ref "D20") (pin "2") (pinfunction "NC_2") (pintype "passive"))
      (node (ref "D20") (pin "3") (pinfunction "PG_3") (pintype "output"))
      (node (ref "D20") (pin "5") (pinfunction "GND_5") (pintype "passive"))
      (node (ref "L27") (pin "1") (pinfunction "1_1") (pintype "passive"))
      (node (ref "R36") (pin "1") (pinfunction "1_1") (pintype "passive"))
      (node (ref "R37") (pin "1") (pinfunction "1_1") (pintype "passive"))
      (node (ref "R41") (pin "1") (pinfunction "1_1") (pintype "passive"))
    )
    (net (code "16") (name "Net-(C97-Pad2)") (class "Default")
      (node (ref "C97") (pin "2") (pinfunction "2_2") (pintype "passive"))
      (node (ref "R38") (pin "1") (pinfunction "1_1") (pintype "passive"))
    )
    (net (code "17") (name "Net-(D13-BOOST)") (class "Default")
      (node (ref "C88") (pin "1") (pinfunction "1_1") (pintype "passive"))
      (node (ref "D13") (pin "13") (pinfunction "BOOST_13") (pintype "passive"))
    )
    (net (code "18") (name "Net-(D13-COMP)") (class "Default")
      (node (ref "D13") (pin "4") (pinfunction "COMP_4") (pintype "passive"))
      (node (ref "R38") (pin "2") (pinfunction "2_2") (pintype "passive"))
    )
    (net (code "19") (name "Net-(D13-FREQ{slash}SYNC)") (class "Default")
      (node (ref "D13") (pin "1") (pinfunction "FREQ/SYNC_1") (pintype "input"))
      (node (ref "R36") (pin "2") (pinfunction "2_2") (pintype "passive"))
    )
    (net (code "20") (name "Net-(D13-ILIMIT)") (class "Default")
      (node (ref "D13") (pin "3") (pinfunction "ILIMIT_3") (pintype "input"))
      (node (ref "R37") (pin "2") (pinfunction "2_2") (pintype "passive"))
    )
    (net (code "21") (name "Net-(D13-SW)") (class "Default")
      (node (ref "C88") (pin "2") (pinfunction "2_2") (pintype "passive"))
      (node (ref "D13") (pin "7") (pinfunction "SW_7") (pintype "passive"))
      (node (ref "L20") (pin "2") (pinfunction "2_2") (pintype "passive"))
    )
    (net (code "22") (name "Net-(D13-VCC)") (class "Default")
      (node (ref "C90") (pin "1") (pinfunction "1_1") (pintype "passive"))
      (node (ref "D13") (pin "10") (pinfunction "VCC_10") (pintype "passive"))
    )
    (net (code "23") (name "TPS_EN") (class "Default")
      (node (ref "D13") (pin "11") (pinfunction "EN_11") (pintype "input"))
    )
    (net (code "24") (name "_1V8") (class "Default")
      (node (ref "C114") (pin "2") (pinfunction "2_2") (pintype "passive"))
      (node (ref "C115") (pin "2") (pinfunction "2_2") (pintype "passive"))
      (node (ref "C120") (pin "1") (pinfunction "1_1") (pintype "passive"))
      (node (ref "C122") (pin "2") (pinfunction "2_2") (pintype "passive"))
      (node (ref "C123") (pin "2") (pinfunction "2_2") (pintype "passive"))
      (node (ref "D18") (pin "1") (pinfunction "OUT_1") (pintype "passive"))
      (node (ref "L24") (pin "1") (pinfunction "1_1") (pintype "passive"))
      (node (ref "L25") (pin "1") (pinfunction "1_1") (pintype "passive"))
    )
    (net (code "25") (name "_3V3") (class "Default")
      (node (ref "C108") (pin "2") (pinfunction "2_2") (pintype "passive"))
      (node (ref "C109") (pin "2") (pinfunction "2_2") (pintype "passive"))
      (node (ref "C128") (pin "1") (pinfunction "1_1") (pintype "passive"))
      (node (ref "C130") (pin "2") (pinfunction "2_2") (pintype "passive"))
      (node (ref "C131") (pin "2") (pinfunction "2_2") (pintype "passive"))
      (node (ref "D20") (pin "1") (pinfunction "OUT_1") (pintype "passive"))
      (node (ref "L23") (pin "1") (pinfunction "1_1") (pintype "passive"))
      (node (ref "L26") (pin "1") (pinfunction "1_1") (pintype "passive"))
    )
    (net (code "26") (name "_3V3_flt") (class "Default")
      (node (ref "C110") (pin "2") (pinfunction "2_2") (pintype "passive"))
      (node (ref "C111") (pin "2") (pinfunction "2_2") (pintype "passive"))
      (node (ref "C112") (pin "2") (pinfunction "2_2") (pintype "passive"))
      (node (ref "D17") (pin "4") (pinfunction "EN_4") (pintype "input"))
      (node (ref "D17") (pin "6") (pinfunction "IN_6") (pintype "passive"))
      (node (ref "L23") (pin "2") (pinfunction "2_2") (pintype "passive"))
    )
    (net (code "27") (name "_5V_flt") (class "Default")
      (node (ref "C101") (pin "2") (pinfunction "2_2") (pintype "passive"))
      (node (ref "C102") (pin "2") (pinfunction "2_2") (pintype "passive"))
      (node (ref "C103") (pin "2") (pinfunction "2_2") (pintype "passive"))
      (node (ref "D14") (pin "4") (pinfunction "EN_4") (pintype "input"))
      (node (ref "D14") (pin "6") (pinfunction "IN_6") (pintype "passive"))
      (node (ref "D19") (pin "4") (pinfunction "EN_4") (pintype "input"))
      (node (ref "D19") (pin "6") (pinfunction "IN_6") (pintype "passive"))
      (node (ref "D21") (pin "4") (pinfunction "EN_4") (pintype "input"))
      (node (ref "D21") (pin "6") (pinfunction "IN_6") (pintype "passive"))
      (node (ref "L22") (pin "2") (pinfunction "2_2") (pintype "passive"))
    )
    (net (code "28") (name "_6V_flt") (class "Default")
      (node (ref "C94") (pin "2") (pinfunction "2_2") (pintype "passive"))
      (node (ref "C95") (pin "2") (pinfunction "2_2") (pintype "passive"))
      (node (ref "C96") (pin "2") (pinfunction "2_2") (pintype "passive"))
      (node (ref "D12") (pin "4") (pinfunction "EN_4") (pintype "input"))
      (node (ref "D12") (pin "6") (pinfunction "IN_6") (pintype "passive"))
      (node (ref "D15") (pin "4") (pinfunction "EN_4") (pintype "input"))
      (node (ref "D15") (pin "6") (pinfunction "IN_6") (pintype "passive"))
      (node (ref "D16") (pin "4") (pinfunction "EN_4") (pintype "input"))
      (node (ref "D16") (pin "6") (pinfunction "IN_6") (pintype "passive"))
      (node (ref "L21") (pin "2") (pinfunction "2_2") (pintype "passive"))
    )
    (net (code "29") (name "_12V_TPS") (class "Default")
      (node (ref "C104") (pin "2") (pinfunction "2_2") (pintype "passive"))
      (node (ref "C84") (pin "2") (pinfunction "2_2") (pintype "passive"))
      (node (ref "L19") (pin "1") (pinfunction "1_1") (pintype "passive"))
      (node (ref "Q1") (pin "2") (pinfunction "S_2") (pintype "passive"))
      (node (ref "R39") (pin "2") (pinfunction "2_2") (pintype "passive"))
    )
    (net (code "30") (name "_TPS_DISDRV") (class "Default")
      (node (ref "C106") (pin "2") (pinfunction "2_2") (pintype "passive"))
      (node (ref "D13") (pin "9") (pinfunction "DISDRV_9") (pintype "passive"))
      (node (ref "Q1") (pin "1") (pinfunction "G_1") (pintype "passive"))
      (node (ref "R40") (pin "1") (pinfunction "1_1") (pintype "passive"))
    )
    (net (code "31") (name "_TPS_FB") (class "Default")
      (node (ref "D13") (pin "5") (pinfunction "FB_5") (pintype "passive"))
      (node (ref "R39") (pin "1") (pinfunction "1_1") (pintype "passive"))
      (node (ref "R41") (pin "2") (pinfunction "2_2") (pintype "passive"))
    )
    (net (code "32") (name "_TPS_VOUT") (class "Default")
      (node (ref "C105") (pin "2") (pinfunction "2_2") (pintype "passive"))
      (node (ref "C106") (pin "1") (pinfunction "1_1") (pintype "passive"))
      (node (ref "D13") (pin "8") (pinfunction "VOUT_8") (pintype "passive"))
      (node (ref "Q1") (pin "3") (pinfunction "D_3") (pintype "passive"))
      (node (ref "R40") (pin "2") (pinfunction "2_2") (pintype "passive"))
    )
  )
)
